# PCIE_Connector.net
KiCad netlist of a schematic drawn in Altium Designer
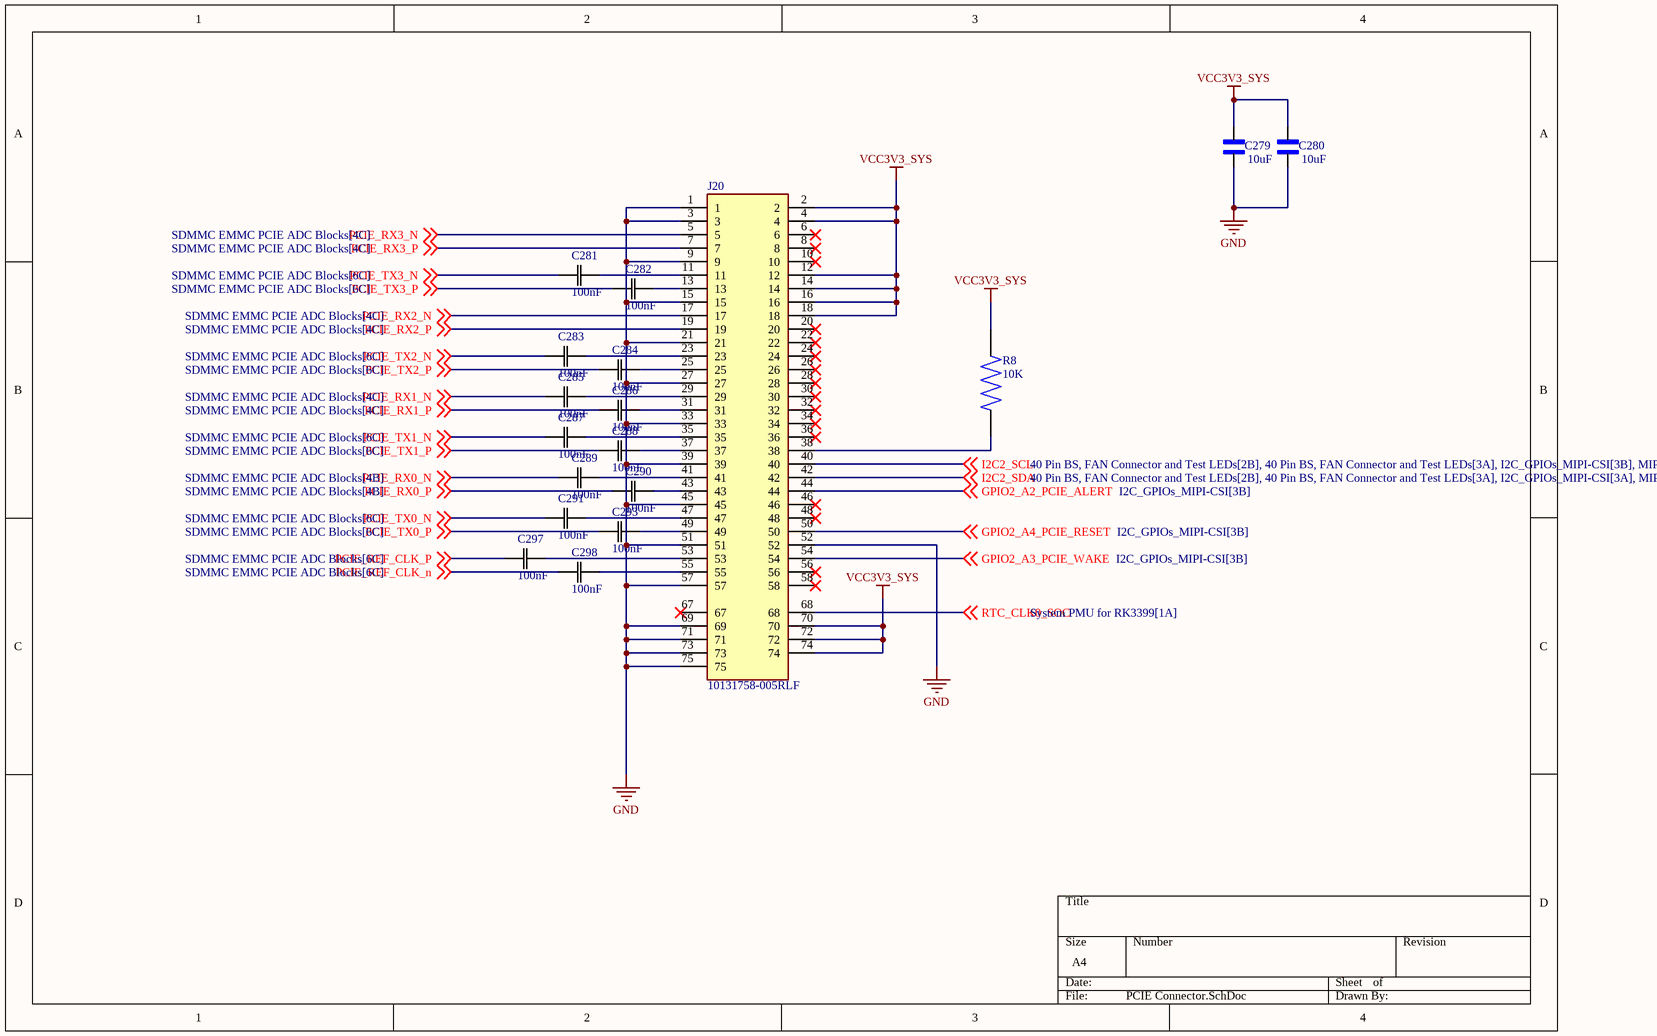
[diagram p0: PCIE Connector.SchDoc]

(export (version "E")
  (design (tool "Eeschema 10.0.6"))
  (components
    (comp (ref "C279")
      (value "10uF")
      (footprint "CAPC1005X70N")
      (description "10 ÂµF Â±20% 6.3V Ceramic Capacitor X5R 0402 (1005 Metric)")
      (fields (field (name "MF") "Samsung") (field (name "MP") "CL05A106MQ5NUNC"))
      (libsource (lib "CL05A106MQ5NUNC") (part "CL05A106MQ5NUNC"))
    )
    (comp (ref "C280")
      (value "10uF")
      (footprint "CAPC1005X70N")
      (description "10 ÂµF Â±20% 6.3V Ceramic Capacitor X5R 0402 (1005 Metric)")
      (fields (field (name "MF") "Samsung") (field (name "MP") "CL05A106MQ5NUNC"))
      (libsource (lib "CL05A106MQ5NUNC") (part "CL05A106MQ5NUNC"))
    )
    (comp (ref "C281")
      (value "100nF")
      (footprint "CAP_1005_TDK")
      (description "Description")
      (fields
        (field (name "MANUFACTURER_PART_NUMBER") "C1005X7R1H104M050BB")
        (field (name "COPYRIGHT") "Copyright (C) 2025 Ultra Librarian. All rights reserved.")
      )
      (libsource (lib "C1005X7R1H104M050BB") (part "C1005X7R1H104M050BB"))
    )
    (comp (ref "C282")
      (value "100nF")
      (footprint "CAP_1005_TDK")
      (description "Description")
      (fields
        (field (name "MANUFACTURER_PART_NUMBER") "C1005X7R1H104M050BB")
        (field (name "COPYRIGHT") "Copyright (C) 2025 Ultra Librarian. All rights reserved.")
      )
      (libsource (lib "C1005X7R1H104M050BB") (part "C1005X7R1H104M050BB"))
    )
    (comp (ref "C283")
      (value "100nF")
      (footprint "CAP_1005_TDK")
      (description "Description")
      (fields
        (field (name "MANUFACTURER_PART_NUMBER") "C1005X7R1H104M050BB")
        (field (name "COPYRIGHT") "Copyright (C) 2025 Ultra Librarian. All rights reserved.")
      )
      (libsource (lib "C1005X7R1H104M050BB") (part "C1005X7R1H104M050BB"))
    )
    (comp (ref "C284")
      (value "100nF")
      (footprint "CAP_1005_TDK")
      (description "Description")
      (fields
        (field (name "MANUFACTURER_PART_NUMBER") "C1005X7R1H104M050BB")
        (field (name "COPYRIGHT") "Copyright (C) 2025 Ultra Librarian. All rights reserved.")
      )
      (libsource (lib "C1005X7R1H104M050BB") (part "C1005X7R1H104M050BB"))
    )
    (comp (ref "C285")
      (value "100nF")
      (footprint "CAP_1005_TDK")
      (description "Description")
      (fields
        (field (name "MANUFACTURER_PART_NUMBER") "C1005X7R1H104M050BB")
        (field (name "COPYRIGHT") "Copyright (C) 2025 Ultra Librarian. All rights reserved.")
      )
      (libsource (lib "C1005X7R1H104M050BB") (part "C1005X7R1H104M050BB"))
    )
    (comp (ref "C286")
      (value "100nF")
      (footprint "CAP_1005_TDK")
      (description "Description")
      (fields
        (field (name "MANUFACTURER_PART_NUMBER") "C1005X7R1H104M050BB")
        (field (name "COPYRIGHT") "Copyright (C) 2025 Ultra Librarian. All rights reserved.")
      )
      (libsource (lib "C1005X7R1H104M050BB") (part "C1005X7R1H104M050BB"))
    )
    (comp (ref "C287")
      (value "100nF")
      (footprint "CAP_1005_TDK")
      (description "Description")
      (fields
        (field (name "MANUFACTURER_PART_NUMBER") "C1005X7R1H104M050BB")
        (field (name "COPYRIGHT") "Copyright (C) 2025 Ultra Librarian. All rights reserved.")
      )
      (libsource (lib "C1005X7R1H104M050BB") (part "C1005X7R1H104M050BB"))
    )
    (comp (ref "C288")
      (value "100nF")
      (footprint "CAP_1005_TDK")
      (description "Description")
      (fields
        (field (name "MANUFACTURER_PART_NUMBER") "C1005X7R1H104M050BB")
        (field (name "COPYRIGHT") "Copyright (C) 2025 Ultra Librarian. All rights reserved.")
      )
      (libsource (lib "C1005X7R1H104M050BB") (part "C1005X7R1H104M050BB"))
    )
    (comp (ref "C289")
      (value "100nF")
      (footprint "CAP_1005_TDK")
      (description "Description")
      (fields
        (field (name "MANUFACTURER_PART_NUMBER") "C1005X7R1H104M050BB")
        (field (name "COPYRIGHT") "Copyright (C) 2025 Ultra Librarian. All rights reserved.")
      )
      (libsource (lib "C1005X7R1H104M050BB") (part "C1005X7R1H104M050BB"))
    )
    (comp (ref "C290")
      (value "100nF")
      (footprint "CAP_1005_TDK")
      (description "Description")
      (fields
        (field (name "MANUFACTURER_PART_NUMBER") "C1005X7R1H104M050BB")
        (field (name "COPYRIGHT") "Copyright (C) 2025 Ultra Librarian. All rights reserved.")
      )
      (libsource (lib "C1005X7R1H104M050BB") (part "C1005X7R1H104M050BB"))
    )
    (comp (ref "C291")
      (value "100nF")
      (footprint "CAP_1005_TDK")
      (description "Description")
      (fields
        (field (name "MANUFACTURER_PART_NUMBER") "C1005X7R1H104M050BB")
        (field (name "COPYRIGHT") "Copyright (C) 2025 Ultra Librarian. All rights reserved.")
      )
      (libsource (lib "C1005X7R1H104M050BB") (part "C1005X7R1H104M050BB"))
    )
    (comp (ref "C293")
      (value "100nF")
      (footprint "CAP_1005_TDK")
      (description "Description")
      (fields
        (field (name "MANUFACTURER_PART_NUMBER") "C1005X7R1H104M050BB")
        (field (name "COPYRIGHT") "Copyright (C) 2025 Ultra Librarian. All rights reserved.")
      )
      (libsource (lib "C1005X7R1H104M050BB") (part "C1005X7R1H104M050BB"))
    )
    (comp (ref "C297")
      (value "100nF")
      (footprint "CAP_1005_TDK")
      (description "Description")
      (fields
        (field (name "MANUFACTURER_PART_NUMBER") "C1005X7R1H104M050BB")
        (field (name "COPYRIGHT") "Copyright (C) 2025 Ultra Librarian. All rights reserved.")
      )
      (libsource (lib "C1005X7R1H104M050BB") (part "C1005X7R1H104M050BB"))
    )
    (comp (ref "C298")
      (value "100nF")
      (footprint "CAP_1005_TDK")
      (description "Description")
      (fields
        (field (name "MANUFACTURER_PART_NUMBER") "C1005X7R1H104M050BB")
        (field (name "COPYRIGHT") "Copyright (C) 2025 Ultra Librarian. All rights reserved.")
      )
      (libsource (lib "C1005X7R1H104M050BB") (part "C1005X7R1H104M050BB"))
    )
    (comp (ref "J20")
      (value "10131758-005RLF")
      (footprint "AMPHENOL_10131758-005RLF")
      (fields (field (name "MF") "Amphenol"))
      (libsource (lib "10131758-005RLF") (part "10131758-005RLF"))
    )
    (comp (ref "R8")
      (value "10K")
      (footprint "RES_ERA3ARB103V")
      (fields (field (name "MP") "ERA3ARB103V"))
      (libsource (lib "ERA3ARB103V") (part "ERA3ARB103V"))
    )
  )
  (nets
    (net (code "1") (name "GND") (class "Default")
      (node (ref "C279") (pin "1") (pinfunction "1_1") (pintype "passive"))
      (node (ref "C280") (pin "1") (pinfunction "1_1") (pintype "passive"))
      (node (ref "J20") (pin "1") (pinfunction "1_1") (pintype "passive"))
      (node (ref "J20") (pin "15") (pinfunction "15_15") (pintype "passive"))
      (node (ref "J20") (pin "21") (pinfunction "21_21") (pintype "passive"))
      (node (ref "J20") (pin "27") (pinfunction "27_27") (pintype "passive"))
      (node (ref "J20") (pin "3") (pinfunction "3_3") (pintype "passive"))
      (node (ref "J20") (pin "33") (pinfunction "33_33") (pintype "passive"))
      (node (ref "J20") (pin "39") (pinfunction "39_39") (pintype "passive"))
      (node (ref "J20") (pin "45") (pinfunction "45_45") (pintype "passive"))
      (node (ref "J20") (pin "51") (pinfunction "51_51") (pintype "passive"))
      (node (ref "J20") (pin "52") (pinfunction "52_52") (pintype "passive"))
      (node (ref "J20") (pin "57") (pinfunction "57_57") (pintype "passive"))
      (node (ref "J20") (pin "69") (pinfunction "69_69") (pintype "passive"))
      (node (ref "J20") (pin "71") (pinfunction "71_71") (pintype "passive"))
      (node (ref "J20") (pin "73") (pinfunction "73_73") (pintype "passive"))
      (node (ref "J20") (pin "75") (pinfunction "75_75") (pintype "passive"))
      (node (ref "J20") (pin "9") (pinfunction "9_9") (pintype "passive"))
    )
    (net (code "2") (name "GPIO2_A2_PCIE_ALERT") (class "Default")
      (node (ref "J20") (pin "44") (pinfunction "44_44") (pintype "passive"))
    )
    (net (code "3") (name "GPIO2_A3_PCIE_WAKE") (class "Default")
      (node (ref "J20") (pin "54") (pinfunction "54_54") (pintype "passive"))
    )
    (net (code "4") (name "GPIO2_A4_PCIE_RESET") (class "Default")
      (node (ref "J20") (pin "50") (pinfunction "50_50") (pintype "passive"))
    )
    (net (code "5") (name "I2C2_SCL") (class "Default")
      (node (ref "J20") (pin "40") (pinfunction "40_40") (pintype "passive"))
    )
    (net (code "6") (name "I2C2_SDA") (class "Default")
      (node (ref "J20") (pin "42") (pinfunction "42_42") (pintype "passive"))
    )
    (net (code "7") (name "Net-(C281-Pad1)") (class "Default")
      (node (ref "C281") (pin "1") (pinfunction "1_1") (pintype "passive"))
      (node (ref "J20") (pin "11") (pinfunction "11_11") (pintype "passive"))
    )
    (net (code "8") (name "Net-(C282-Pad1)") (class "Default")
      (node (ref "C282") (pin "1") (pinfunction "1_1") (pintype "passive"))
      (node (ref "J20") (pin "13") (pinfunction "13_13") (pintype "passive"))
    )
    (net (code "9") (name "Net-(C283-Pad1)") (class "Default")
      (node (ref "C283") (pin "1") (pinfunction "1_1") (pintype "passive"))
      (node (ref "J20") (pin "23") (pinfunction "23_23") (pintype "passive"))
    )
    (net (code "10") (name "Net-(C284-Pad1)") (class "Default")
      (node (ref "C284") (pin "1") (pinfunction "1_1") (pintype "passive"))
      (node (ref "J20") (pin "25") (pinfunction "25_25") (pintype "passive"))
    )
    (net (code "11") (name "Net-(C285-Pad1)") (class "Default")
      (node (ref "C285") (pin "1") (pinfunction "1_1") (pintype "passive"))
      (node (ref "J20") (pin "29") (pinfunction "29_29") (pintype "passive"))
    )
    (net (code "12") (name "Net-(C286-Pad1)") (class "Default")
      (node (ref "C286") (pin "1") (pinfunction "1_1") (pintype "passive"))
      (node (ref "J20") (pin "31") (pinfunction "31_31") (pintype "passive"))
    )
    (net (code "13") (name "Net-(C287-Pad1)") (class "Default")
      (node (ref "C287") (pin "1") (pinfunction "1_1") (pintype "passive"))
      (node (ref "J20") (pin "35") (pinfunction "35_35") (pintype "passive"))
    )
    (net (code "14") (name "Net-(C288-Pad1)") (class "Default")
      (node (ref "C288") (pin "1") (pinfunction "1_1") (pintype "passive"))
      (node (ref "J20") (pin "37") (pinfunction "37_37") (pintype "passive"))
    )
    (net (code "15") (name "Net-(C289-Pad1)") (class "Default")
      (node (ref "C289") (pin "1") (pinfunction "1_1") (pintype "passive"))
      (node (ref "J20") (pin "41") (pinfunction "41_41") (pintype "passive"))
    )
    (net (code "16") (name "Net-(C290-Pad1)") (class "Default")
      (node (ref "C290") (pin "1") (pinfunction "1_1") (pintype "passive"))
      (node (ref "J20") (pin "43") (pinfunction "43_43") (pintype "passive"))
    )
    (net (code "17") (name "Net-(C291-Pad1)") (class "Default")
      (node (ref "C291") (pin "1") (pinfunction "1_1") (pintype "passive"))
      (node (ref "J20") (pin "47") (pinfunction "47_47") (pintype "passive"))
    )
    (net (code "18") (name "Net-(C293-Pad1)") (class "Default")
      (node (ref "C293") (pin "1") (pinfunction "1_1") (pintype "passive"))
      (node (ref "J20") (pin "49") (pinfunction "49_49") (pintype "passive"))
    )
    (net (code "19") (name "Net-(C297-Pad1)") (class "Default")
      (node (ref "C297") (pin "1") (pinfunction "1_1") (pintype "passive"))
      (node (ref "J20") (pin "53") (pinfunction "53_53") (pintype "passive"))
    )
    (net (code "20") (name "Net-(C298-Pad1)") (class "Default")
      (node (ref "C298") (pin "1") (pinfunction "1_1") (pintype "passive"))
      (node (ref "J20") (pin "55") (pinfunction "55_55") (pintype "passive"))
    )
    (net (code "21") (name "Net-(J20-Pad38)") (class "Default")
      (node (ref "J20") (pin "38") (pinfunction "38_38") (pintype "passive"))
      (node (ref "R8") (pin "2") (pinfunction "2_2") (pintype "passive"))
    )
    (net (code "22") (name "PCIE_REF_CLK_P") (class "Default")
      (node (ref "C297") (pin "2") (pinfunction "2_2") (pintype "passive"))
    )
    (net (code "23") (name "PCIE_REF_CLK_n") (class "Default")
      (node (ref "C298") (pin "2") (pinfunction "2_2") (pintype "passive"))
    )
    (net (code "24") (name "PCIE_RX0_N") (class "Default")
      (node (ref "C289") (pin "2") (pinfunction "2_2") (pintype "passive"))
    )
    (net (code "25") (name "PCIE_RX0_P") (class "Default")
      (node (ref "C290") (pin "2") (pinfunction "2_2") (pintype "passive"))
    )
    (net (code "26") (name "PCIE_RX1_N") (class "Default")
      (node (ref "C285") (pin "2") (pinfunction "2_2") (pintype "passive"))
    )
    (net (code "27") (name "PCIE_RX1_P") (class "Default")
      (node (ref "C286") (pin "2") (pinfunction "2_2") (pintype "passive"))
    )
    (net (code "28") (name "PCIE_RX2_N") (class "Default")
      (node (ref "J20") (pin "17") (pinfunction "17_17") (pintype "passive"))
    )
    (net (code "29") (name "PCIE_RX2_P") (class "Default")
      (node (ref "J20") (pin "19") (pinfunction "19_19") (pintype "passive"))
    )
    (net (code "30") (name "PCIE_RX3_N") (class "Default")
      (node (ref "J20") (pin "5") (pinfunction "5_5") (pintype "passive"))
    )
    (net (code "31") (name "PCIE_RX3_P") (class "Default")
      (node (ref "J20") (pin "7") (pinfunction "7_7") (pintype "passive"))
    )
    (net (code "32") (name "PCIE_TX0_N") (class "Default")
      (node (ref "C291") (pin "2") (pinfunction "2_2") (pintype "passive"))
    )
    (net (code "33") (name "PCIE_TX0_P") (class "Default")
      (node (ref "C293") (pin "2") (pinfunction "2_2") (pintype "passive"))
    )
    (net (code "34") (name "PCIE_TX1_N") (class "Default")
      (node (ref "C287") (pin "2") (pinfunction "2_2") (pintype "passive"))
    )
    (net (code "35") (name "PCIE_TX1_P") (class "Default")
      (node (ref "C288") (pin "2") (pinfunction "2_2") (pintype "passive"))
    )
    (net (code "36") (name "PCIE_TX2_N") (class "Default")
      (node (ref "C283") (pin "2") (pinfunction "2_2") (pintype "passive"))
    )
    (net (code "37") (name "PCIE_TX2_P") (class "Default")
      (node (ref "C284") (pin "2") (pinfunction "2_2") (pintype "passive"))
    )
    (net (code "38") (name "PCIE_TX3_N") (class "Default")
      (node (ref "C281") (pin "2") (pinfunction "2_2") (pintype "passive"))
    )
    (net (code "39") (name "PCIE_TX3_P") (class "Default")
      (node (ref "C282") (pin "2") (pinfunction "2_2") (pintype "passive"))
    )
    (net (code "40") (name "RTC_CLK0_SOC") (class "Default")
      (node (ref "J20") (pin "68") (pinfunction "68_68") (pintype "passive"))
    )
    (net (code "41") (name "VCC3V3_SYS") (class "Default")
      (node (ref "C279") (pin "2") (pinfunction "2_2") (pintype "passive"))
      (node (ref "C280") (pin "2") (pinfunction "2_2") (pintype "passive"))
      (node (ref "J20") (pin "12") (pinfunction "12_12") (pintype "passive"))
      (node (ref "J20") (pin "14") (pinfunction "14_14") (pintype "passive"))
      (node (ref "J20") (pin "16") (pinfunction "16_16") (pintype "passive"))
      (node (ref "J20") (pin "18") (pinfunction "18_18") (pintype "passive"))
      (node (ref "J20") (pin "2") (pinfunction "2_2") (pintype "passive"))
      (node (ref "J20") (pin "4") (pinfunction "4_4") (pintype "passive"))
      (node (ref "J20") (pin "70") (pinfunction "70_70") (pintype "passive"))
      (node (ref "J20") (pin "72") (pinfunction "72_72") (pintype "passive"))
      (node (ref "J20") (pin "74") (pinfunction "74_74") (pintype "passive"))
      (node (ref "R8") (pin "1") (pinfunction "1_1") (pintype "passive"))
    )
    (net (code "42") (name "unconnected-(J20-Pad6)") (class "Default")
      (node (ref "J20") (pin "6") (pinfunction "6_6") (pintype "passive+no_connect"))
    )
    (net (code "43") (name "unconnected-(J20-Pad8)") (class "Default")
      (node (ref "J20") (pin "8") (pinfunction "8_8") (pintype "passive+no_connect"))
    )
    (net (code "44") (name "unconnected-(J20-Pad10)") (class "Default")
      (node (ref "J20") (pin "10") (pinfunction "10_10") (pintype "passive+no_connect"))
    )
    (net (code "45") (name "unconnected-(J20-Pad20)") (class "Default")
      (node (ref "J20") (pin "20") (pinfunction "20_20") (pintype "passive+no_connect"))
    )
    (net (code "46") (name "unconnected-(J20-Pad22)") (class "Default")
      (node (ref "J20") (pin "22") (pinfunction "22_22") (pintype "passive+no_connect"))
    )
    (net (code "47") (name "unconnected-(J20-Pad24)") (class "Default")
      (node (ref "J20") (pin "24") (pinfunction "24_24") (pintype "passive+no_connect"))
    )
    (net (code "48") (name "unconnected-(J20-Pad26)") (class "Default")
      (node (ref "J20") (pin "26") (pinfunction "26_26") (pintype "passive+no_connect"))
    )
    (net (code "49") (name "unconnected-(J20-Pad28)") (class "Default")
      (node (ref "J20") (pin "28") (pinfunction "28_28") (pintype "passive+no_connect"))
    )
    (net (code "50") (name "unconnected-(J20-Pad30)") (class "Default")
      (node (ref "J20") (pin "30") (pinfunction "30_30") (pintype "passive+no_connect"))
    )
    (net (code "51") (name "unconnected-(J20-Pad32)") (class "Default")
      (node (ref "J20") (pin "32") (pinfunction "32_32") (pintype "passive+no_connect"))
    )
    (net (code "52") (name "unconnected-(J20-Pad34)") (class "Default")
      (node (ref "J20") (pin "34") (pinfunction "34_34") (pintype "passive+no_connect"))
    )
    (net (code "53") (name "unconnected-(J20-Pad36)") (class "Default")
      (node (ref "J20") (pin "36") (pinfunction "36_36") (pintype "passive+no_connect"))
    )
    (net (code "54") (name "unconnected-(J20-Pad46)") (class "Default")
      (node (ref "J20") (pin "46") (pinfunction "46_46") (pintype "passive+no_connect"))
    )
    (net (code "55") (name "unconnected-(J20-Pad48)") (class "Default")
      (node (ref "J20") (pin "48") (pinfunction "48_48") (pintype "passive+no_connect"))
    )
    (net (code "56") (name "unconnected-(J20-Pad56)") (class "Default")
      (node (ref "J20") (pin "56") (pinfunction "56_56") (pintype "passive+no_connect"))
    )
    (net (code "57") (name "unconnected-(J20-Pad58)") (class "Default")
      (node (ref "J20") (pin "58") (pinfunction "58_58") (pintype "passive+no_connect"))
    )
    (net (code "58") (name "unconnected-(J20-Pad67)") (class "Default")
      (node (ref "J20") (pin "67") (pinfunction "67_67") (pintype "passive+no_connect"))
    )
  )
)
